# I2S_ADC_OPTION.net
KiCad netlist of a schematic drawn in Altium Designer
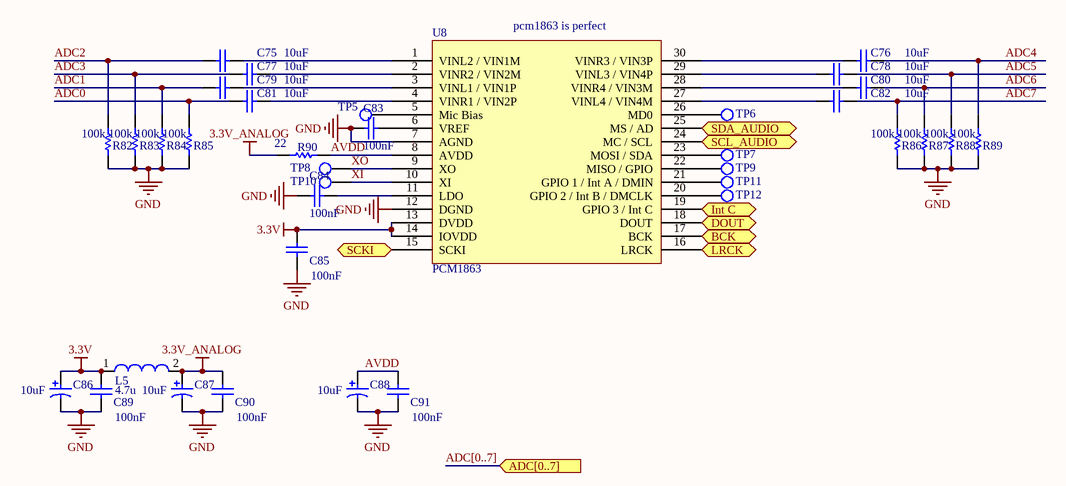
[diagram p0: I2S_ADC_OPTION.SchDoc]

(export (version "E")
  (design (tool "Eeschema 10.0.6"))
  (components
    (comp (ref "C75")
      (value "10uF")
      (footprint "CAPC0402(1005)60_L")
      (description "0402 (1005 Metric) Chip Capacitor")
      (fields (field (name "Comment") "CAP0402"))
      (libsource (lib "Altium Content Vault") (part "CMP-1590-00004-1"))
    )
    (comp (ref "C76")
      (value "10uF")
      (footprint "CAPC0402(1005)60_L")
      (description "0402 (1005 Metric) Chip Capacitor")
      (fields (field (name "Comment") "CAP0402"))
      (libsource (lib "Altium Content Vault") (part "CMP-1590-00004-1"))
    )
    (comp (ref "C77")
      (value "10uF")
      (footprint "CAPC0402(1005)60_L")
      (description "0402 (1005 Metric) Chip Capacitor")
      (fields (field (name "Comment") "CAP0402"))
      (libsource (lib "Altium Content Vault") (part "CMP-1590-00004-1"))
    )
    (comp (ref "C78")
      (value "10uF")
      (footprint "CAPC0402(1005)60_L")
      (description "0402 (1005 Metric) Chip Capacitor")
      (fields (field (name "Comment") "CAP0402"))
      (libsource (lib "Altium Content Vault") (part "CMP-1590-00004-1"))
    )
    (comp (ref "C79")
      (value "10uF")
      (footprint "CAPC0402(1005)60_L")
      (description "0402 (1005 Metric) Chip Capacitor")
      (fields (field (name "Comment") "CAP0402"))
      (libsource (lib "Altium Content Vault") (part "CMP-1590-00004-1"))
    )
    (comp (ref "C80")
      (value "10uF")
      (footprint "CAPC0402(1005)60_L")
      (description "0402 (1005 Metric) Chip Capacitor")
      (fields (field (name "Comment") "CAP0402"))
      (libsource (lib "Altium Content Vault") (part "CMP-1590-00004-1"))
    )
    (comp (ref "C81")
      (value "10uF")
      (footprint "CAPC0402(1005)60_L")
      (description "0402 (1005 Metric) Chip Capacitor")
      (fields (field (name "Comment") "CAP0402"))
      (libsource (lib "Altium Content Vault") (part "CMP-1590-00004-1"))
    )
    (comp (ref "C82")
      (value "10uF")
      (footprint "CAPC0402(1005)60_L")
      (description "0402 (1005 Metric) Chip Capacitor")
      (fields (field (name "Comment") "CAP0402"))
      (libsource (lib "Altium Content Vault") (part "CMP-1590-00004-1"))
    )
    (comp (ref "C83")
      (value "100nF")
      (footprint "CAPC0402(1005)60_L")
      (description "0402 (1005 Metric) Chip Capacitor")
      (fields (field (name "Comment") "CAP0402"))
      (libsource (lib "Altium Content Vault") (part "CMP-1590-00004-1"))
    )
    (comp (ref "C84")
      (value "100nF")
      (footprint "CAPC0402(1005)60_L")
      (description "0402 (1005 Metric) Chip Capacitor")
      (fields (field (name "Comment") "CAP0402"))
      (libsource (lib "Altium Content Vault") (part "CMP-1590-00004-1"))
    )
    (comp (ref "C85")
      (value "100nF")
      (footprint "CAPC0402(1005)60_L")
      (description "0402 (1005 Metric) Chip Capacitor")
      (fields (field (name "Comment") "CAP0402"))
      (libsource (lib "Altium Content Vault") (part "CMP-1590-00004-1"))
    )
    (comp (ref "C86")
      (value "T491A106K016AT")
      (footprint "KEMT-A-3216-18-2_M")
      (description "Capacitor, Tantalum, 10 uF, +/- 10%, 16 V, -55 to 125 degC, 2-Pin SMD (1206), RoHS, Tape and Reel")
      (fields
        (field (name "VOLTAGE") "16VDC")
        (field (name "CAPACITANCE") "10uF")
        (field (name "MANUFACTURER") "Kemet")
      )
      (libsource (lib "Altium Content Vault") (part "CMP-2000-05173-1"))
    )
    (comp (ref "C87")
      (value "T491A106K016AT")
      (footprint "KEMT-A-3216-18-2_M")
      (description "Capacitor, Tantalum, 10 uF, +/- 10%, 16 V, -55 to 125 degC, 2-Pin SMD (1206), RoHS, Tape and Reel")
      (fields
        (field (name "VOLTAGE") "16VDC")
        (field (name "CAPACITANCE") "10uF")
        (field (name "MANUFACTURER") "Kemet")
      )
      (libsource (lib "Altium Content Vault") (part "CMP-2000-05173-1"))
    )
    (comp (ref "C88")
      (value "T491A106K016AT")
      (footprint "KEMT-A-3216-18-2_M")
      (description "Capacitor, Tantalum, 10 uF, +/- 10%, 16 V, -55 to 125 degC, 2-Pin SMD (1206), RoHS, Tape and Reel")
      (fields
        (field (name "VOLTAGE") "16VDC")
        (field (name "CAPACITANCE") "10uF")
        (field (name "MANUFACTURER") "Kemet")
      )
      (libsource (lib "Altium Content Vault") (part "CMP-2000-05173-1"))
    )
    (comp (ref "C89")
      (value "100nF")
      (footprint "CAPC0402(1005)60_L")
      (description "0402 (1005 Metric) Chip Capacitor")
      (fields (field (name "Comment") "CAP0402"))
      (libsource (lib "Altium Content Vault") (part "CMP-1590-00004-1"))
    )
    (comp (ref "C90")
      (value "100nF")
      (footprint "CAPC0402(1005)60_L")
      (description "0402 (1005 Metric) Chip Capacitor")
      (fields (field (name "Comment") "CAP0402"))
      (libsource (lib "Altium Content Vault") (part "CMP-1590-00004-1"))
    )
    (comp (ref "C91")
      (value "100nF")
      (footprint "CAPC0402(1005)60_L")
      (description "0402 (1005 Metric) Chip Capacitor")
      (fields (field (name "Comment") "CAP0402"))
      (libsource (lib "Altium Content Vault") (part "CMP-1590-00004-1"))
    )
    (comp (ref "L5")
      (value "TYS50204R7N-10")
      (footprint "TYS5020220M-10")
      (fields
        (field (name "MANUFACTURER") "Wurth Elektronik")
        (field (name "L") "4.7u")
        (field (name "CREATED BY") "Baojun Chen")
      )
      (libsource (lib "Kilian_UCC_Library") (part "TYS50204R7N-10"))
    )
    (comp (ref "R82")
      (value "100k")
      (footprint "RESC0402(1005)_L")
      (description "0402 (1005 Metric) Chip Resistor")
      (fields (field (name "Comment") "RES0402"))
      (libsource (lib "Altium Content Vault") (part "CMP-1591-00004-1"))
    )
    (comp (ref "R83")
      (value "100k")
      (footprint "RESC0402(1005)_L")
      (description "0402 (1005 Metric) Chip Resistor")
      (fields (field (name "Comment") "RES0402"))
      (libsource (lib "Altium Content Vault") (part "CMP-1591-00004-1"))
    )
    (comp (ref "R84")
      (value "100k")
      (footprint "RESC0402(1005)_L")
      (description "0402 (1005 Metric) Chip Resistor")
      (fields (field (name "Comment") "RES0402"))
      (libsource (lib "Altium Content Vault") (part "CMP-1591-00004-1"))
    )
    (comp (ref "R85")
      (value "100k")
      (footprint "RESC0402(1005)_L")
      (description "0402 (1005 Metric) Chip Resistor")
      (fields (field (name "Comment") "RES0402"))
      (libsource (lib "Altium Content Vault") (part "CMP-1591-00004-1"))
    )
    (comp (ref "R86")
      (value "100k")
      (footprint "RESC0402(1005)_L")
      (description "0402 (1005 Metric) Chip Resistor")
      (fields (field (name "Comment") "RES0402"))
      (libsource (lib "Altium Content Vault") (part "CMP-1591-00004-1"))
    )
    (comp (ref "R87")
      (value "100k")
      (footprint "RESC0402(1005)_L")
      (description "0402 (1005 Metric) Chip Resistor")
      (fields (field (name "Comment") "RES0402"))
      (libsource (lib "Altium Content Vault") (part "CMP-1591-00004-1"))
    )
    (comp (ref "R88")
      (value "100k")
      (footprint "RESC0402(1005)_L")
      (description "0402 (1005 Metric) Chip Resistor")
      (fields (field (name "Comment") "RES0402"))
      (libsource (lib "Altium Content Vault") (part "CMP-1591-00004-1"))
    )
    (comp (ref "R89")
      (value "100k")
      (footprint "RESC0402(1005)_L")
      (description "0402 (1005 Metric) Chip Resistor")
      (fields (field (name "Comment") "RES0402"))
      (libsource (lib "Altium Content Vault") (part "CMP-1591-00004-1"))
    )
    (comp (ref "R90")
      (value "22")
      (footprint "RESC0402(1005)_L")
      (description "0402 (1005 Metric) Chip Resistor")
      (fields (field (name "Comment") "RES0402"))
      (libsource (lib "Altium Content Vault") (part "CMP-1591-00004-1"))
    )
    (comp (ref "TP5")
      (value "Test Point")
      (footprint "Test_Point")
      (description "HARWIN  S1751-46R  PCB Test Point, S1751 Series, Surface Mount, Copper Alloy, Tin Plated Contacts")
      (fields (field (name "MANUFACTURER") "HARWIN") (field (name "MANUFACTURER PART NUMBER") "S1751-46R"))
      (libsource (lib "Kilian_UCC_Library") (part "Test_Point"))
    )
    (comp (ref "TP6")
      (value "Test Point")
      (footprint "Test_Point")
      (description "HARWIN  S1751-46R  PCB Test Point, S1751 Series, Surface Mount, Copper Alloy, Tin Plated Contacts")
      (fields (field (name "MANUFACTURER") "HARWIN") (field (name "MANUFACTURER PART NUMBER") "S1751-46R"))
      (libsource (lib "Kilian_UCC_Library") (part "Test_Point"))
    )
    (comp (ref "TP7")
      (value "Test Point")
      (footprint "Test_Point")
      (description "HARWIN  S1751-46R  PCB Test Point, S1751 Series, Surface Mount, Copper Alloy, Tin Plated Contacts")
      (fields (field (name "MANUFACTURER") "HARWIN") (field (name "MANUFACTURER PART NUMBER") "S1751-46R"))
      (libsource (lib "Kilian_UCC_Library") (part "Test_Point"))
    )
    (comp (ref "TP8")
      (value "Test Point")
      (footprint "Test_Point")
      (description "HARWIN  S1751-46R  PCB Test Point, S1751 Series, Surface Mount, Copper Alloy, Tin Plated Contacts")
      (fields (field (name "MANUFACTURER") "HARWIN") (field (name "MANUFACTURER PART NUMBER") "S1751-46R"))
      (libsource (lib "Kilian_UCC_Library") (part "Test_Point"))
    )
    (comp (ref "TP9")
      (value "Test Point")
      (footprint "Test_Point")
      (description "HARWIN  S1751-46R  PCB Test Point, S1751 Series, Surface Mount, Copper Alloy, Tin Plated Contacts")
      (fields (field (name "MANUFACTURER") "HARWIN") (field (name "MANUFACTURER PART NUMBER") "S1751-46R"))
      (libsource (lib "Kilian_UCC_Library") (part "Test_Point"))
    )
    (comp (ref "TP10")
      (value "Test Point")
      (footprint "Test_Point")
      (description "HARWIN  S1751-46R  PCB Test Point, S1751 Series, Surface Mount, Copper Alloy, Tin Plated Contacts")
      (fields (field (name "MANUFACTURER") "HARWIN") (field (name "MANUFACTURER PART NUMBER") "S1751-46R"))
      (libsource (lib "Kilian_UCC_Library") (part "Test_Point"))
    )
    (comp (ref "TP11")
      (value "Test Point")
      (footprint "Test_Point")
      (description "HARWIN  S1751-46R  PCB Test Point, S1751 Series, Surface Mount, Copper Alloy, Tin Plated Contacts")
      (fields (field (name "MANUFACTURER") "HARWIN") (field (name "MANUFACTURER PART NUMBER") "S1751-46R"))
      (libsource (lib "Kilian_UCC_Library") (part "Test_Point"))
    )
    (comp (ref "TP12")
      (value "Test Point")
      (footprint "Test_Point")
      (description "HARWIN  S1751-46R  PCB Test Point, S1751 Series, Surface Mount, Copper Alloy, Tin Plated Contacts")
      (fields (field (name "MANUFACTURER") "HARWIN") (field (name "MANUFACTURER PART NUMBER") "S1751-46R"))
      (libsource (lib "Kilian_UCC_Library") (part "Test_Point"))
    )
    (comp (ref "U8")
      (value "PCM1863")
      (footprint "TSSOP30")
      (fields
        (field (name "MANUFACTURER") "Texas Instruments")
        (field (name "MANUFACTURER PART NUMBER") "PCM1863DBTR")
      )
      (libsource (lib "DAQ_Replacement") (part "PCM1863"))
    )
  )
  (nets
    (net (code "1") (name "/ADC0") (class "Default")
      (node (ref "C81") (pin "1") (pinfunction "1_1") (pintype "passive"))
      (node (ref "R85") (pin "2") (pinfunction "2_2") (pintype "passive"))
    )
    (net (code "2") (name "/ADC1") (class "Default")
      (node (ref "C79") (pin "1") (pinfunction "1_1") (pintype "passive"))
      (node (ref "R84") (pin "2") (pinfunction "2_2") (pintype "passive"))
    )
    (net (code "3") (name "/ADC2") (class "Default")
      (node (ref "C75") (pin "1") (pinfunction "1_1") (pintype "passive"))
      (node (ref "R82") (pin "2") (pinfunction "2_2") (pintype "passive"))
    )
    (net (code "4") (name "/ADC3") (class "Default")
      (node (ref "C77") (pin "1") (pinfunction "1_1") (pintype "passive"))
      (node (ref "R83") (pin "2") (pinfunction "2_2") (pintype "passive"))
    )
    (net (code "5") (name "/ADC4") (class "Default")
      (node (ref "C78") (pin "2") (pinfunction "2_2") (pintype "passive"))
      (node (ref "R89") (pin "2") (pinfunction "2_2") (pintype "passive"))
    )
    (net (code "6") (name "/ADC5") (class "Default")
      (node (ref "C76") (pin "2") (pinfunction "2_2") (pintype "passive"))
      (node (ref "R88") (pin "2") (pinfunction "2_2") (pintype "passive"))
    )
    (net (code "7") (name "/ADC6") (class "Default")
      (node (ref "C80") (pin "2") (pinfunction "2_2") (pintype "passive"))
      (node (ref "R87") (pin "2") (pinfunction "2_2") (pintype "passive"))
    )
    (net (code "8") (name "/ADC7") (class "Default")
      (node (ref "C82") (pin "2") (pinfunction "2_2") (pintype "passive"))
      (node (ref "R86") (pin "2") (pinfunction "2_2") (pintype "passive"))
    )
    (net (code "10") (name "/AVDD") (class "Default")
      (node (ref "C88") (pin "1") (pinfunction "1_1") (pintype "passive"))
      (node (ref "C91") (pin "1") (pinfunction "1_1") (pintype "passive"))
      (node (ref "R90") (pin "1") (pinfunction "1_1") (pintype "passive"))
      (node (ref "U8") (pin "8") (pinfunction "AVDD_8") (pintype "passive"))
    )
    (net (code "11") (name "/BCK") (class "Default")
      (node (ref "U8") (pin "17") (pinfunction "BCK_17") (pintype "passive"))
    )
    (net (code "12") (name "/DOUT") (class "Default")
      (node (ref "U8") (pin "18") (pinfunction "DOUT_18") (pintype "passive"))
    )
    (net (code "13") (name "/Int C") (class "Default")
      (node (ref "U8") (pin "19") (pinfunction "GPIO_3_/_Int_C_19") (pintype "passive"))
    )
    (net (code "14") (name "/LRCK") (class "Default")
      (node (ref "U8") (pin "16") (pinfunction "LRCK_16") (pintype "passive"))
    )
    (net (code "15") (name "/SCKI") (class "Default")
      (node (ref "U8") (pin "15") (pinfunction "SCKI_15") (pintype "passive"))
    )
    (net (code "16") (name "/SCL_AUDIO") (class "Default")
      (node (ref "U8") (pin "24") (pinfunction "MC_/_SCL_24") (pintype "passive"))
    )
    (net (code "17") (name "/SDA_AUDIO") (class "Default")
      (node (ref "U8") (pin "25") (pinfunction "MS_/_AD_25") (pintype "passive"))
    )
    (net (code "18") (name "/XI") (class "Default")
      (node (ref "TP10") (pin "1") (pinfunction "TP_1") (pintype "passive"))
      (node (ref "U8") (pin "10") (pinfunction "XI_10") (pintype "passive"))
    )
    (net (code "19") (name "/XO") (class "Default")
      (node (ref "TP8") (pin "1") (pinfunction "TP_1") (pintype "passive"))
      (node (ref "U8") (pin "9") (pinfunction "XO_9") (pintype "passive"))
    )
    (net (code "20") (name "3.3V") (class "Default")
      (node (ref "C85") (pin "1") (pinfunction "1_1") (pintype "passive"))
      (node (ref "C86") (pin "1") (pinfunction "1_1") (pintype "passive"))
      (node (ref "C89") (pin "1") (pinfunction "1_1") (pintype "passive"))
      (node (ref "L5") (pin "1") (pinfunction "1_1") (pintype "passive"))
      (node (ref "U8") (pin "13") (pinfunction "DVDD_13") (pintype "passive"))
      (node (ref "U8") (pin "14") (pinfunction "IOVDD_14") (pintype "passive"))
    )
    (net (code "21") (name "3.3V_ANALOG") (class "Default")
      (node (ref "C87") (pin "1") (pinfunction "1_1") (pintype "passive"))
      (node (ref "C90") (pin "1") (pinfunction "1_1") (pintype "passive"))
      (node (ref "L5") (pin "2") (pinfunction "2_2") (pintype "passive"))
      (node (ref "R90") (pin "2") (pinfunction "2_2") (pintype "passive"))
    )
    (net (code "22") (name "GND") (class "Default")
      (node (ref "C83") (pin "1") (pinfunction "1_1") (pintype "passive"))
      (node (ref "C84") (pin "1") (pinfunction "1_1") (pintype "passive"))
      (node (ref "C85") (pin "2") (pinfunction "2_2") (pintype "passive"))
      (node (ref "C86") (pin "2") (pinfunction "2_2") (pintype "passive"))
      (node (ref "C87") (pin "2") (pinfunction "2_2") (pintype "passive"))
      (node (ref "C88") (pin "2") (pinfunction "2_2") (pintype "passive"))
      (node (ref "C89") (pin "2") (pinfunction "2_2") (pintype "passive"))
      (node (ref "C90") (pin "2") (pinfunction "2_2") (pintype "passive"))
      (node (ref "C91") (pin "2") (pinfunction "2_2") (pintype "passive"))
      (node (ref "R82") (pin "1") (pinfunction "1_1") (pintype "passive"))
      (node (ref "R83") (pin "1") (pinfunction "1_1") (pintype "passive"))
      (node (ref "R84") (pin "1") (pinfunction "1_1") (pintype "passive"))
      (node (ref "R85") (pin "1") (pinfunction "1_1") (pintype "passive"))
      (node (ref "R86") (pin "1") (pinfunction "1_1") (pintype "passive"))
      (node (ref "R87") (pin "1") (pinfunction "1_1") (pintype "passive"))
      (node (ref "R88") (pin "1") (pinfunction "1_1") (pintype "passive"))
      (node (ref "R89") (pin "1") (pinfunction "1_1") (pintype "passive"))
      (node (ref "U8") (pin "12") (pinfunction "DGND_12") (pintype "passive"))
      (node (ref "U8") (pin "7") (pinfunction "AGND_7") (pintype "passive"))
    )
    (net (code "23") (name "Net-(TP5-TP)") (class "Default")
      (node (ref "TP5") (pin "1") (pinfunction "TP_1") (pintype "passive"))
      (node (ref "U8") (pin "5") (pinfunction "Mic_Bias_5") (pintype "passive"))
    )
    (net (code "24") (name "Net-(TP6-TP)") (class "Default")
      (node (ref "TP6") (pin "1") (pinfunction "TP_1") (pintype "passive"))
      (node (ref "U8") (pin "26") (pinfunction "MD0_26") (pintype "passive"))
    )
    (net (code "25") (name "Net-(TP7-TP)") (class "Default")
      (node (ref "TP7") (pin "1") (pinfunction "TP_1") (pintype "passive"))
      (node (ref "U8") (pin "23") (pinfunction "MOSI_/_SDA_23") (pintype "passive"))
    )
    (net (code "26") (name "Net-(TP9-TP)") (class "Default")
      (node (ref "TP9") (pin "1") (pinfunction "TP_1") (pintype "passive"))
      (node (ref "U8") (pin "22") (pinfunction "MISO_/_GPIO_22") (pintype "passive"))
    )
    (net (code "27") (name "Net-(TP11-TP)") (class "Default")
      (node (ref "TP11") (pin "1") (pinfunction "TP_1") (pintype "passive"))
      (node (ref "U8") (pin "21") (pinfunction "GPIO_1_/_Int_A_/_DMIN_21") (pintype "passive"))
    )
    (net (code "28") (name "Net-(TP12-TP)") (class "Default")
      (node (ref "TP12") (pin "1") (pinfunction "TP_1") (pintype "passive"))
      (node (ref "U8") (pin "20") (pinfunction "GPIO_2_/_Int_B_/_DMCLK_20") (pintype "passive"))
    )
    (net (code "29") (name "Net-(U8-LDO)") (class "Default")
      (node (ref "C84") (pin "2") (pinfunction "2_2") (pintype "passive"))
      (node (ref "U8") (pin "11") (pinfunction "LDO_11") (pintype "passive"))
    )
    (net (code "30") (name "Net-(U8-VINL1_{slash}_VIN1P)") (class "Default")
      (node (ref "C79") (pin "2") (pinfunction "2_2") (pintype "passive"))
      (node (ref "U8") (pin "3") (pinfunction "VINL1_/_VIN1P_3") (pintype "passive"))
    )
    (net (code "31") (name "Net-(U8-VINL2_{slash}_VIN1M)") (class "Default")
      (node (ref "C75") (pin "2") (pinfunction "2_2") (pintype "passive"))
      (node (ref "U8") (pin "1") (pinfunction "VINL2_/_VIN1M_1") (pintype "passive"))
    )
    (net (code "32") (name "Net-(U8-VINL3_{slash}_VIN4P)") (class "Default")
      (node (ref "C76") (pin "1") (pinfunction "1_1") (pintype "passive"))
      (node (ref "U8") (pin "29") (pinfunction "VINL3_/_VIN4P_29") (pintype "passive"))
    )
    (net (code "33") (name "Net-(U8-VINL4_{slash}_VIN4M)") (class "Default")
      (node (ref "C82") (pin "1") (pinfunction "1_1") (pintype "passive"))
      (node (ref "U8") (pin "27") (pinfunction "VINL4_/_VIN4M_27") (pintype "passive"))
    )
    (net (code "34") (name "Net-(U8-VINR1_{slash}_VIN2P)") (class "Default")
      (node (ref "C81") (pin "2") (pinfunction "2_2") (pintype "passive"))
      (node (ref "U8") (pin "4") (pinfunction "VINR1_/_VIN2P_4") (pintype "passive"))
    )
    (net (code "35") (name "Net-(U8-VINR2_{slash}_VIN2M)") (class "Default")
      (node (ref "C77") (pin "2") (pinfunction "2_2") (pintype "passive"))
      (node (ref "U8") (pin "2") (pinfunction "VINR2_/_VIN2M_2") (pintype "passive"))
    )
    (net (code "36") (name "Net-(U8-VINR3_{slash}_VIN3P)") (class "Default")
      (node (ref "C78") (pin "1") (pinfunction "1_1") (pintype "passive"))
      (node (ref "U8") (pin "30") (pinfunction "VINR3_/_VIN3P_30") (pintype "passive"))
    )
    (net (code "37") (name "Net-(U8-VINR4_{slash}_VIN3M)") (class "Default")
      (node (ref "C80") (pin "1") (pinfunction "1_1") (pintype "passive"))
      (node (ref "U8") (pin "28") (pinfunction "VINR4_/_VIN3M_28") (pintype "passive"))
    )
    (net (code "38") (name "Net-(U8-VREF)") (class "Default")
      (node (ref "C83") (pin "2") (pinfunction "2_2") (pintype "passive"))
      (node (ref "U8") (pin "6") (pinfunction "VREF_6") (pintype "passive"))
    )
  )
)
